# BB_cape.net
KiCad netlist of a schematic drawn in Altium Designer
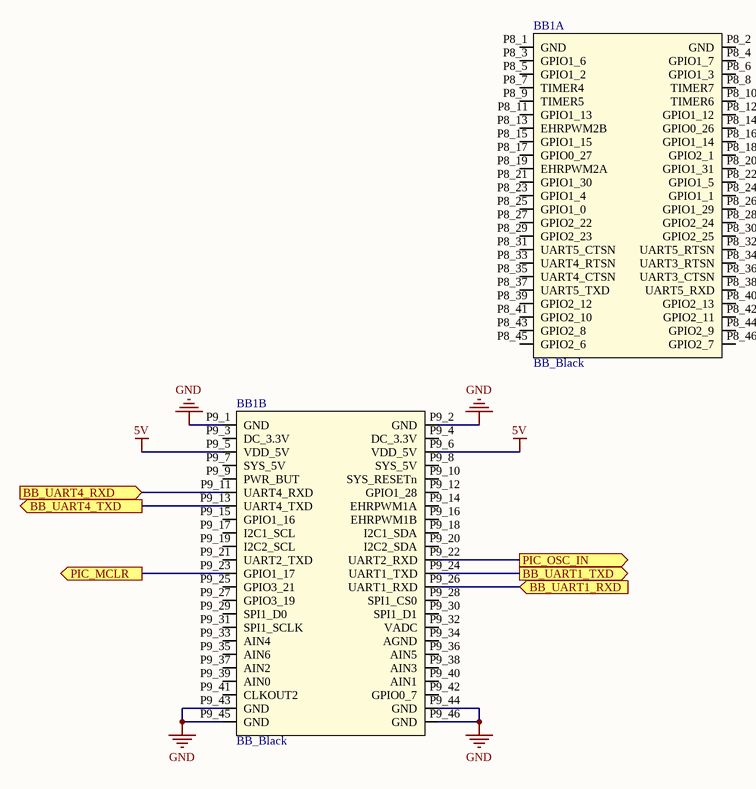
[diagram p0: BB_cape.SchDoc]

(export (version "E")
  (design (tool "Eeschema 10.0.6"))
  (components
    (comp (ref "BB1")
      (value "BB_Black")
      (footprint "BB_Black_Above")
      (libsource (lib "Controllers") (part "BB_Black"))
    )
  )
  (nets
    (net (code "1") (name "/BB_UART1_RXD") (class "Default")
      (node (ref "BB1") (pin "P9_26") (pinfunction "UART1_RXD_P9_26") (pintype "passive"))
    )
    (net (code "2") (name "/BB_UART1_TXD") (class "Default")
      (node (ref "BB1") (pin "P9_24") (pinfunction "UART1_TXD_P9_24") (pintype "passive"))
    )
    (net (code "3") (name "/BB_UART4_RXD") (class "Default")
      (node (ref "BB1") (pin "P9_11") (pinfunction "UART4_RXD_P9_11") (pintype "passive"))
    )
    (net (code "4") (name "/BB_UART4_TXD") (class "Default")
      (node (ref "BB1") (pin "P9_13") (pinfunction "UART4_TXD_P9_13") (pintype "passive"))
    )
    (net (code "5") (name "/PIC_MCLR") (class "Default")
      (node (ref "BB1") (pin "P9_23") (pinfunction "GPIO1_17_P9_23") (pintype "passive"))
    )
    (net (code "6") (name "/PIC_OSC_IN") (class "Default")
      (node (ref "BB1") (pin "P9_22") (pinfunction "UART2_RXD_P9_22") (pintype "passive"))
    )
    (net (code "7") (name "5V") (class "Default")
      (node (ref "BB1") (pin "P9_5") (pinfunction "VDD_5V_P9_5") (pintype "passive"))
      (node (ref "BB1") (pin "P9_6") (pinfunction "VDD_5V_P9_6") (pintype "passive"))
    )
    (net (code "8") (name "GND") (class "Default")
      (node (ref "BB1") (pin "P9_1") (pinfunction "GND_P9_1") (pintype "passive"))
      (node (ref "BB1") (pin "P9_2") (pinfunction "GND_P9_2") (pintype "passive"))
      (node (ref "BB1") (pin "P9_43") (pinfunction "GND_P9_43") (pintype "passive"))
      (node (ref "BB1") (pin "P9_44") (pinfunction "GND_P9_44") (pintype "passive"))
      (node (ref "BB1") (pin "P9_45") (pinfunction "GND_P9_45") (pintype "passive"))
      (node (ref "BB1") (pin "P9_46") (pinfunction "GND_P9_46") (pintype "passive"))
    )
    (net (code "9") (name "unconnected-(BB1A-EHRPWM2A-PadP8_19)") (class "Default")
      (node (ref "BB1") (pin "P8_19") (pinfunction "EHRPWM2A_P8_19") (pintype "passive"))
    )
    (net (code "10") (name "unconnected-(BB1A-EHRPWM2B-PadP8_13)") (class "Default")
      (node (ref "BB1") (pin "P8_13") (pinfunction "EHRPWM2B_P8_13") (pintype "passive"))
    )
    (net (code "11") (name "unconnected-(BB1A-GND-PadP8_1)") (class "Default")
      (node (ref "BB1") (pin "P8_1") (pinfunction "GND_P8_1") (pintype "passive"))
    )
    (net (code "12") (name "unconnected-(BB1A-GND-PadP8_2)") (class "Default")
      (node (ref "BB1") (pin "P8_2") (pinfunction "GND_P8_2") (pintype "passive"))
    )
    (net (code "13") (name "unconnected-(BB1A-GPIO0_26-PadP8_14)") (class "Default")
      (node (ref "BB1") (pin "P8_14") (pinfunction "GPIO0_26_P8_14") (pintype "passive"))
    )
    (net (code "14") (name "unconnected-(BB1A-GPIO0_27-PadP8_17)") (class "Default")
      (node (ref "BB1") (pin "P8_17") (pinfunction "GPIO0_27_P8_17") (pintype "passive"))
    )
    (net (code "15") (name "unconnected-(BB1A-GPIO1_0-PadP8_25)") (class "Default")
      (node (ref "BB1") (pin "P8_25") (pinfunction "GPIO1_0_P8_25") (pintype "passive"))
    )
    (net (code "16") (name "unconnected-(BB1A-GPIO1_1-PadP8_24)") (class "Default")
      (node (ref "BB1") (pin "P8_24") (pinfunction "GPIO1_1_P8_24") (pintype "passive"))
    )
    (net (code "17") (name "unconnected-(BB1A-GPIO1_2-PadP8_5)") (class "Default")
      (node (ref "BB1") (pin "P8_5") (pinfunction "GPIO1_2_P8_5") (pintype "passive"))
    )
    (net (code "18") (name "unconnected-(BB1A-GPIO1_3-PadP8_6)") (class "Default")
      (node (ref "BB1") (pin "P8_6") (pinfunction "GPIO1_3_P8_6") (pintype "passive"))
    )
    (net (code "19") (name "unconnected-(BB1A-GPIO1_4-PadP8_23)") (class "Default")
      (node (ref "BB1") (pin "P8_23") (pinfunction "GPIO1_4_P8_23") (pintype "passive"))
    )
    (net (code "20") (name "unconnected-(BB1A-GPIO1_5-PadP8_22)") (class "Default")
      (node (ref "BB1") (pin "P8_22") (pinfunction "GPIO1_5_P8_22") (pintype "passive"))
    )
    (net (code "21") (name "unconnected-(BB1A-GPIO1_6-PadP8_3)") (class "Default")
      (node (ref "BB1") (pin "P8_3") (pinfunction "GPIO1_6_P8_3") (pintype "passive"))
    )
    (net (code "22") (name "unconnected-(BB1A-GPIO1_7-PadP8_4)") (class "Default")
      (node (ref "BB1") (pin "P8_4") (pinfunction "GPIO1_7_P8_4") (pintype "passive"))
    )
    (net (code "23") (name "unconnected-(BB1A-GPIO1_12-PadP8_12)") (class "Default")
      (node (ref "BB1") (pin "P8_12") (pinfunction "GPIO1_12_P8_12") (pintype "passive"))
    )
    (net (code "24") (name "unconnected-(BB1A-GPIO1_13-PadP8_11)") (class "Default")
      (node (ref "BB1") (pin "P8_11") (pinfunction "GPIO1_13_P8_11") (pintype "passive"))
    )
    (net (code "25") (name "unconnected-(BB1A-GPIO1_14-PadP8_16)") (class "Default")
      (node (ref "BB1") (pin "P8_16") (pinfunction "GPIO1_14_P8_16") (pintype "passive"))
    )
    (net (code "26") (name "unconnected-(BB1A-GPIO1_15-PadP8_15)") (class "Default")
      (node (ref "BB1") (pin "P8_15") (pinfunction "GPIO1_15_P8_15") (pintype "passive"))
    )
    (net (code "27") (name "unconnected-(BB1A-GPIO1_29-PadP8_26)") (class "Default")
      (node (ref "BB1") (pin "P8_26") (pinfunction "GPIO1_29_P8_26") (pintype "passive"))
    )
    (net (code "28") (name "unconnected-(BB1A-GPIO1_30-PadP8_21)") (class "Default")
      (node (ref "BB1") (pin "P8_21") (pinfunction "GPIO1_30_P8_21") (pintype "passive"))
    )
    (net (code "29") (name "unconnected-(BB1A-GPIO1_31-PadP8_20)") (class "Default")
      (node (ref "BB1") (pin "P8_20") (pinfunction "GPIO1_31_P8_20") (pintype "passive"))
    )
    (net (code "30") (name "unconnected-(BB1A-GPIO2_1-PadP8_18)") (class "Default")
      (node (ref "BB1") (pin "P8_18") (pinfunction "GPIO2_1_P8_18") (pintype "passive"))
    )
    (net (code "31") (name "unconnected-(BB1A-GPIO2_6-PadP8_45)") (class "Default")
      (node (ref "BB1") (pin "P8_45") (pinfunction "GPIO2_6_P8_45") (pintype "passive"))
    )
    (net (code "32") (name "unconnected-(BB1A-GPIO2_7-PadP8_46)") (class "Default")
      (node (ref "BB1") (pin "P8_46") (pinfunction "GPIO2_7_P8_46") (pintype "passive"))
    )
    (net (code "33") (name "unconnected-(BB1A-GPIO2_8-PadP8_43)") (class "Default")
      (node (ref "BB1") (pin "P8_43") (pinfunction "GPIO2_8_P8_43") (pintype "passive"))
    )
    (net (code "34") (name "unconnected-(BB1A-GPIO2_9-PadP8_44)") (class "Default")
      (node (ref "BB1") (pin "P8_44") (pinfunction "GPIO2_9_P8_44") (pintype "passive"))
    )
    (net (code "35") (name "unconnected-(BB1A-GPIO2_10-PadP8_41)") (class "Default")
      (node (ref "BB1") (pin "P8_41") (pinfunction "GPIO2_10_P8_41") (pintype "passive"))
    )
    (net (code "36") (name "unconnected-(BB1A-GPIO2_11-PadP8_42)") (class "Default")
      (node (ref "BB1") (pin "P8_42") (pinfunction "GPIO2_11_P8_42") (pintype "passive"))
    )
    (net (code "37") (name "unconnected-(BB1A-GPIO2_12-PadP8_39)") (class "Default")
      (node (ref "BB1") (pin "P8_39") (pinfunction "GPIO2_12_P8_39") (pintype "passive"))
    )
    (net (code "38") (name "unconnected-(BB1A-GPIO2_13-PadP8_40)") (class "Default")
      (node (ref "BB1") (pin "P8_40") (pinfunction "GPIO2_13_P8_40") (pintype "passive"))
    )
    (net (code "39") (name "unconnected-(BB1A-GPIO2_22-PadP8_27)") (class "Default")
      (node (ref "BB1") (pin "P8_27") (pinfunction "GPIO2_22_P8_27") (pintype "passive"))
    )
    (net (code "40") (name "unconnected-(BB1A-GPIO2_23-PadP8_29)") (class "Default")
      (node (ref "BB1") (pin "P8_29") (pinfunction "GPIO2_23_P8_29") (pintype "passive"))
    )
    (net (code "41") (name "unconnected-(BB1A-GPIO2_24-PadP8_28)") (class "Default")
      (node (ref "BB1") (pin "P8_28") (pinfunction "GPIO2_24_P8_28") (pintype "passive"))
    )
    (net (code "42") (name "unconnected-(BB1A-GPIO2_25-PadP8_30)") (class "Default")
      (node (ref "BB1") (pin "P8_30") (pinfunction "GPIO2_25_P8_30") (pintype "passive"))
    )
    (net (code "43") (name "unconnected-(BB1A-TIMER4-PadP8_7)") (class "Default")
      (node (ref "BB1") (pin "P8_7") (pinfunction "TIMER4_P8_7") (pintype "passive"))
    )
    (net (code "44") (name "unconnected-(BB1A-TIMER5-PadP8_9)") (class "Default")
      (node (ref "BB1") (pin "P8_9") (pinfunction "TIMER5_P8_9") (pintype "passive"))
    )
    (net (code "45") (name "unconnected-(BB1A-TIMER6-PadP8_10)") (class "Default")
      (node (ref "BB1") (pin "P8_10") (pinfunction "TIMER6_P8_10") (pintype "passive"))
    )
    (net (code "46") (name "unconnected-(BB1A-TIMER7-PadP8_8)") (class "Default")
      (node (ref "BB1") (pin "P8_8") (pinfunction "TIMER7_P8_8") (pintype "passive"))
    )
    (net (code "47") (name "unconnected-(BB1A-UART3_CTSN-PadP8_36)") (class "Default")
      (node (ref "BB1") (pin "P8_36") (pinfunction "UART3_CTSN_P8_36") (pintype "passive"))
    )
    (net (code "48") (name "unconnected-(BB1A-UART3_RTSN-PadP8_34)") (class "Default")
      (node (ref "BB1") (pin "P8_34") (pinfunction "UART3_RTSN_P8_34") (pintype "passive"))
    )
    (net (code "49") (name "unconnected-(BB1A-UART4_CTSN-PadP8_35)") (class "Default")
      (node (ref "BB1") (pin "P8_35") (pinfunction "UART4_CTSN_P8_35") (pintype "passive"))
    )
    (net (code "50") (name "unconnected-(BB1A-UART4_RTSN-PadP8_33)") (class "Default")
      (node (ref "BB1") (pin "P8_33") (pinfunction "UART4_RTSN_P8_33") (pintype "passive"))
    )
    (net (code "51") (name "unconnected-(BB1A-UART5_CTSN-PadP8_31)") (class "Default")
      (node (ref "BB1") (pin "P8_31") (pinfunction "UART5_CTSN_P8_31") (pintype "passive"))
    )
    (net (code "52") (name "unconnected-(BB1A-UART5_RTSN-PadP8_32)") (class "Default")
      (node (ref "BB1") (pin "P8_32") (pinfunction "UART5_RTSN_P8_32") (pintype "passive"))
    )
    (net (code "53") (name "unconnected-(BB1A-UART5_RXD-PadP8_38)") (class "Default")
      (node (ref "BB1") (pin "P8_38") (pinfunction "UART5_RXD_P8_38") (pintype "passive"))
    )
    (net (code "54") (name "unconnected-(BB1A-UART5_TXD-PadP8_37)") (class "Default")
      (node (ref "BB1") (pin "P8_37") (pinfunction "UART5_TXD_P8_37") (pintype "passive"))
    )
    (net (code "55") (name "unconnected-(BB1B-AGND-PadP9_34)") (class "Default")
      (node (ref "BB1") (pin "P9_34") (pinfunction "AGND_P9_34") (pintype "passive"))
    )
    (net (code "56") (name "unconnected-(BB1B-AIN0-PadP9_39)") (class "Default")
      (node (ref "BB1") (pin "P9_39") (pinfunction "AIN0_P9_39") (pintype "passive"))
    )
    (net (code "57") (name "unconnected-(BB1B-AIN1-PadP9_40)") (class "Default")
      (node (ref "BB1") (pin "P9_40") (pinfunction "AIN1_P9_40") (pintype "passive"))
    )
    (net (code "58") (name "unconnected-(BB1B-AIN2-PadP9_37)") (class "Default")
      (node (ref "BB1") (pin "P9_37") (pinfunction "AIN2_P9_37") (pintype "passive"))
    )
    (net (code "59") (name "unconnected-(BB1B-AIN3-PadP9_38)") (class "Default")
      (node (ref "BB1") (pin "P9_38") (pinfunction "AIN3_P9_38") (pintype "passive"))
    )
    (net (code "60") (name "unconnected-(BB1B-AIN4-PadP9_33)") (class "Default")
      (node (ref "BB1") (pin "P9_33") (pinfunction "AIN4_P9_33") (pintype "passive"))
    )
    (net (code "61") (name "unconnected-(BB1B-AIN5-PadP9_36)") (class "Default")
      (node (ref "BB1") (pin "P9_36") (pinfunction "AIN5_P9_36") (pintype "passive"))
    )
    (net (code "62") (name "unconnected-(BB1B-AIN6-PadP9_35)") (class "Default")
      (node (ref "BB1") (pin "P9_35") (pinfunction "AIN6_P9_35") (pintype "passive"))
    )
    (net (code "63") (name "unconnected-(BB1B-CLKOUT2-PadP9_41)") (class "Default")
      (node (ref "BB1") (pin "P9_41") (pinfunction "CLKOUT2_P9_41") (pintype "passive"))
    )
    (net (code "64") (name "unconnected-(BB1B-DC_3.3V-PadP9_3)") (class "Default")
      (node (ref "BB1") (pin "P9_3") (pinfunction "DC_3.3V_P9_3") (pintype "passive"))
    )
    (net (code "65") (name "unconnected-(BB1B-DC_3.3V-PadP9_4)") (class "Default")
      (node (ref "BB1") (pin "P9_4") (pinfunction "DC_3.3V_P9_4") (pintype "passive"))
    )
    (net (code "66") (name "unconnected-(BB1B-EHRPWM1A-PadP9_14)") (class "Default")
      (node (ref "BB1") (pin "P9_14") (pinfunction "EHRPWM1A_P9_14") (pintype "passive"))
    )
    (net (code "67") (name "unconnected-(BB1B-EHRPWM1B-PadP9_16)") (class "Default")
      (node (ref "BB1") (pin "P9_16") (pinfunction "EHRPWM1B_P9_16") (pintype "passive"))
    )
    (net (code "68") (name "unconnected-(BB1B-GPIO0_7-PadP9_42)") (class "Default")
      (node (ref "BB1") (pin "P9_42") (pinfunction "GPIO0_7_P9_42") (pintype "passive"))
    )
    (net (code "69") (name "unconnected-(BB1B-GPIO1_16-PadP9_15)") (class "Default")
      (node (ref "BB1") (pin "P9_15") (pinfunction "GPIO1_16_P9_15") (pintype "passive"))
    )
    (net (code "70") (name "unconnected-(BB1B-GPIO1_28-PadP9_12)") (class "Default")
      (node (ref "BB1") (pin "P9_12") (pinfunction "GPIO1_28_P9_12") (pintype "passive"))
    )
    (net (code "71") (name "unconnected-(BB1B-GPIO3_19-PadP9_27)") (class "Default")
      (node (ref "BB1") (pin "P9_27") (pinfunction "GPIO3_19_P9_27") (pintype "passive"))
    )
    (net (code "72") (name "unconnected-(BB1B-GPIO3_21-PadP9_25)") (class "Default")
      (node (ref "BB1") (pin "P9_25") (pinfunction "GPIO3_21_P9_25") (pintype "passive"))
    )
    (net (code "73") (name "unconnected-(BB1B-I2C1_SCL-PadP9_17)") (class "Default")
      (node (ref "BB1") (pin "P9_17") (pinfunction "I2C1_SCL_P9_17") (pintype "passive"))
    )
    (net (code "74") (name "unconnected-(BB1B-I2C1_SDA-PadP9_18)") (class "Default")
      (node (ref "BB1") (pin "P9_18") (pinfunction "I2C1_SDA_P9_18") (pintype "passive"))
    )
    (net (code "75") (name "unconnected-(BB1B-I2C2_SCL-PadP9_19)") (class "Default")
      (node (ref "BB1") (pin "P9_19") (pinfunction "I2C2_SCL_P9_19") (pintype "passive"))
    )
    (net (code "76") (name "unconnected-(BB1B-I2C2_SDA-PadP9_20)") (class "Default")
      (node (ref "BB1") (pin "P9_20") (pinfunction "I2C2_SDA_P9_20") (pintype "passive"))
    )
    (net (code "77") (name "unconnected-(BB1B-PWR_BUT-PadP9_9)") (class "Default")
      (node (ref "BB1") (pin "P9_9") (pinfunction "PWR_BUT_P9_9") (pintype "passive"))
    )
    (net (code "78") (name "unconnected-(BB1B-SPI1_CS0-PadP9_28)") (class "Default")
      (node (ref "BB1") (pin "P9_28") (pinfunction "SPI1_CS0_P9_28") (pintype "passive"))
    )
    (net (code "79") (name "unconnected-(BB1B-SPI1_D0-PadP9_29)") (class "Default")
      (node (ref "BB1") (pin "P9_29") (pinfunction "SPI1_D0_P9_29") (pintype "passive"))
    )
    (net (code "80") (name "unconnected-(BB1B-SPI1_D1-PadP9_30)") (class "Default")
      (node (ref "BB1") (pin "P9_30") (pinfunction "SPI1_D1_P9_30") (pintype "passive"))
    )
    (net (code "81") (name "unconnected-(BB1B-SPI1_SCLK-PadP9_31)") (class "Default")
      (node (ref "BB1") (pin "P9_31") (pinfunction "SPI1_SCLK_P9_31") (pintype "passive"))
    )
    (net (code "82") (name "unconnected-(BB1B-SYS_5V-PadP9_7)") (class "Default")
      (node (ref "BB1") (pin "P9_7") (pinfunction "SYS_5V_P9_7") (pintype "passive"))
    )
    (net (code "83") (name "unconnected-(BB1B-SYS_5V-PadP9_8)") (class "Default")
      (node (ref "BB1") (pin "P9_8") (pinfunction "SYS_5V_P9_8") (pintype "passive"))
    )
    (net (code "84") (name "unconnected-(BB1B-SYS_RESETn-PadP9_10)") (class "Default")
      (node (ref "BB1") (pin "P9_10") (pinfunction "SYS_RESETn_P9_10") (pintype "passive"))
    )
    (net (code "85") (name "unconnected-(BB1B-UART2_TXD-PadP9_21)") (class "Default")
      (node (ref "BB1") (pin "P9_21") (pinfunction "UART2_TXD_P9_21") (pintype "passive"))
    )
    (net (code "86") (name "unconnected-(BB1B-VADC-PadP9_32)") (class "Default")
      (node (ref "BB1") (pin "P9_32") (pinfunction "VADC_P9_32") (pintype "passive"))
    )
  )
)
